# ASD2811.net
KiCad netlist of a schematic drawn in EAGLE
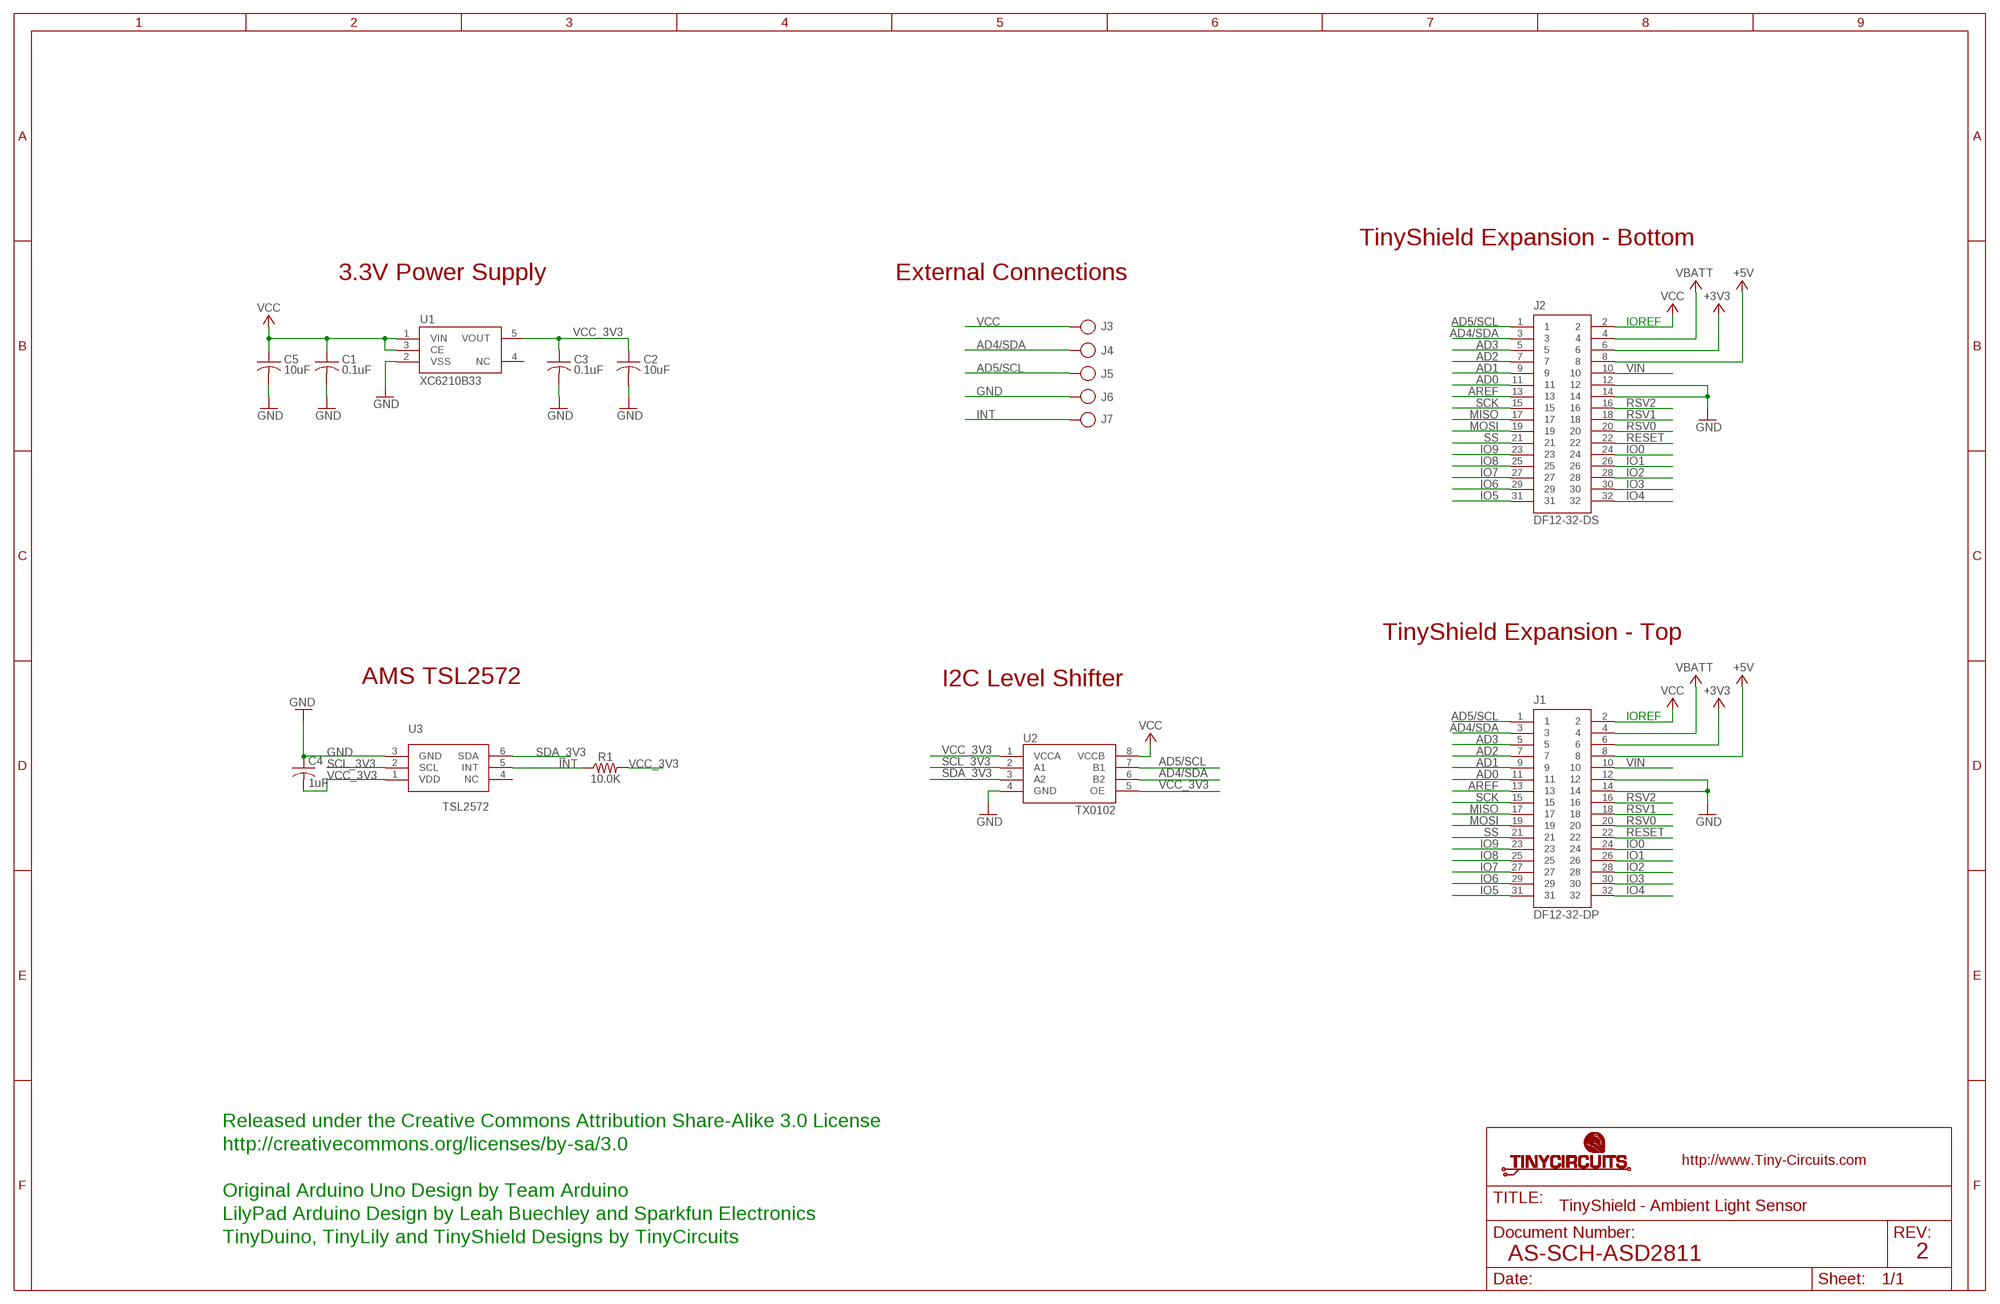
[diagram p0: schematic, sheet 1]

(export (version "E")
  (design (tool "Eeschema 10.0.6"))
  (components
    (comp (ref "C1")
      (value "0.1uF")
      (footprint "eagle-import:C0402")
      (fields (field (name "PARTNO") "AS-ITM-00008") (field (name "PARTNO_1") "AS-ITM-00008"))
      (libsource (lib "eagle-import") (part "AS-ITM-00008"))
    )
    (comp (ref "C2")
      (value "10uF")
      (footprint "eagle-import:C0805")
      (fields (field (name "PARTNO") "AS-ITM-00045") (field (name "PARTNO_1") "AS-ITM-00045"))
      (libsource (lib "eagle-import") (part "AS-ITM-00045"))
    )
    (comp (ref "C3")
      (value "0.1uF")
      (footprint "eagle-import:C0402")
      (fields (field (name "PARTNO") "AS-ITM-00008") (field (name "PARTNO_1") "AS-ITM-00008"))
      (libsource (lib "eagle-import") (part "AS-ITM-00008"))
    )
    (comp (ref "C4")
      (value "1uF")
      (footprint "eagle-import:C0402")
      (fields (field (name "PARTNO") "AS-ITM-00105"))
      (libsource (lib "eagle-import") (part "AS-ITM-00105"))
    )
    (comp (ref "C5")
      (value "10uF")
      (footprint "eagle-import:C0805")
      (fields (field (name "PARTNO") "AS-ITM-00045"))
      (libsource (lib "eagle-import") (part "AS-ITM-00045"))
    )
    (comp (ref "J1")
      (value "DF12-32-DP")
      (footprint "eagle-import:DF12-32-DP")
      (fields (field (name "PARTNO") "AS-ITM-00015") (field (name "PARTNO_1") "AS-ITM-00015"))
      (libsource (lib "eagle-import") (part "AS-ITM-00015"))
    )
    (comp (ref "J2")
      (value "DF12-32-DS")
      (footprint "eagle-import:DF12-32-DS")
      (fields (field (name "PARTNO") "AS-ITM-00012") (field (name "PARTNO_1") "AS-ITM-00012"))
      (libsource (lib "eagle-import") (part "AS-ITM-00012"))
    )
    (comp (ref "J3")
      (value "PIN_1X.1\"")
      (footprint "eagle-import:1X.1_")
      (libsource (lib "eagle-import") (part "PIN_1X.1{dblquote}"))
    )
    (comp (ref "J4")
      (value "PIN_1X.1\"")
      (footprint "eagle-import:1X.1_")
      (libsource (lib "eagle-import") (part "PIN_1X.1{dblquote}"))
    )
    (comp (ref "J5")
      (value "PIN_1X.1\"")
      (footprint "eagle-import:1X.1_")
      (libsource (lib "eagle-import") (part "PIN_1X.1{dblquote}"))
    )
    (comp (ref "J6")
      (value "PIN_1X.1\"")
      (footprint "eagle-import:1X.1_")
      (libsource (lib "eagle-import") (part "PIN_1X.1{dblquote}"))
    )
    (comp (ref "J7")
      (value "PIN_1X.1\"")
      (footprint "eagle-import:1X.1_")
      (libsource (lib "eagle-import") (part "PIN_1X.1{dblquote}"))
    )
    (comp (ref "R1")
      (value "10.0K")
      (footprint "eagle-import:0402")
      (fields (field (name "PARTNO") "AS-ITM-00032"))
      (libsource (lib "eagle-import") (part "AS-ITM-00032"))
    )
    (comp (ref "U1")
      (value "XC6210B33")
      (footprint "eagle-import:SOT-25")
      (fields (field (name "PARTNO") "AS-ITM-00046"))
      (libsource (lib "eagle-import") (part "AS-ITM-00046"))
    )
    (comp (ref "U2")
      (value "TX0102")
      (footprint "eagle-import:DQE(R-PX2SON-N8)")
      (fields (field (name "PARTNO") "AS-ITM-00073"))
      (libsource (lib "eagle-import") (part "AS-ITM-00073"))
    )
    (comp (ref "U3")
      (value "TSL2572")
      (footprint "eagle-import:TSL2572")
      (libsource (lib "eagle-import") (part "AS-ITM-00116"))
    )
  )
  (nets
    (net (code "1") (name "+3V3") (class "Default")
      (node (ref "J1") (pin "6") (pinfunction "6_6") (pintype "bidirectional"))
      (node (ref "J2") (pin "6") (pinfunction "6_6") (pintype "bidirectional"))
    )
    (net (code "2") (name "+5V") (class "Default")
      (node (ref "J1") (pin "8") (pinfunction "8_8") (pintype "bidirectional"))
      (node (ref "J2") (pin "8") (pinfunction "8_8") (pintype "bidirectional"))
    )
    (net (code "3") (name "/AD0") (class "Default")
      (node (ref "J1") (pin "11") (pinfunction "11_11") (pintype "bidirectional"))
      (node (ref "J2") (pin "11") (pinfunction "11_11") (pintype "bidirectional"))
    )
    (net (code "4") (name "/AD1") (class "Default")
      (node (ref "J1") (pin "9") (pinfunction "9_9") (pintype "bidirectional"))
      (node (ref "J2") (pin "9") (pinfunction "9_9") (pintype "bidirectional"))
    )
    (net (code "5") (name "/AD2") (class "Default")
      (node (ref "J1") (pin "7") (pinfunction "7_7") (pintype "bidirectional"))
      (node (ref "J2") (pin "7") (pinfunction "7_7") (pintype "bidirectional"))
    )
    (net (code "6") (name "/AD3") (class "Default")
      (node (ref "J1") (pin "5") (pinfunction "5_5") (pintype "bidirectional"))
      (node (ref "J2") (pin "5") (pinfunction "5_5") (pintype "bidirectional"))
    )
    (net (code "7") (name "/AD4{slash}SDA") (class "Default")
      (node (ref "J1") (pin "3") (pinfunction "3_3") (pintype "bidirectional"))
      (node (ref "J2") (pin "3") (pinfunction "3_3") (pintype "bidirectional"))
      (node (ref "J4") (pin "1") (pinfunction "1_1") (pintype "bidirectional"))
      (node (ref "U2") (pin "6") (pinfunction "B2_6") (pintype "bidirectional"))
    )
    (net (code "8") (name "/AD5{slash}SCL") (class "Default")
      (node (ref "J1") (pin "1") (pinfunction "1_1") (pintype "bidirectional"))
      (node (ref "J2") (pin "1") (pinfunction "1_1") (pintype "bidirectional"))
      (node (ref "J5") (pin "1") (pinfunction "1_1") (pintype "bidirectional"))
      (node (ref "U2") (pin "7") (pinfunction "B1_7") (pintype "bidirectional"))
    )
    (net (code "9") (name "/AREF") (class "Default")
      (node (ref "J1") (pin "13") (pinfunction "13_13") (pintype "bidirectional"))
      (node (ref "J2") (pin "13") (pinfunction "13_13") (pintype "bidirectional"))
    )
    (net (code "10") (name "/INT") (class "Default")
      (node (ref "J7") (pin "1") (pinfunction "1_1") (pintype "bidirectional"))
      (node (ref "R1") (pin "1") (pinfunction "1_1") (pintype "passive"))
      (node (ref "U3") (pin "5") (pinfunction "INT_5") (pintype "bidirectional"))
    )
    (net (code "11") (name "/IO0") (class "Default")
      (node (ref "J1") (pin "24") (pinfunction "24_24") (pintype "bidirectional"))
      (node (ref "J2") (pin "24") (pinfunction "24_24") (pintype "bidirectional"))
    )
    (net (code "12") (name "/IO1") (class "Default")
      (node (ref "J1") (pin "26") (pinfunction "26_26") (pintype "bidirectional"))
      (node (ref "J2") (pin "26") (pinfunction "26_26") (pintype "bidirectional"))
    )
    (net (code "13") (name "/IO2") (class "Default")
      (node (ref "J1") (pin "28") (pinfunction "28_28") (pintype "bidirectional"))
      (node (ref "J2") (pin "28") (pinfunction "28_28") (pintype "bidirectional"))
    )
    (net (code "14") (name "/IO3") (class "Default")
      (node (ref "J1") (pin "30") (pinfunction "30_30") (pintype "bidirectional"))
      (node (ref "J2") (pin "30") (pinfunction "30_30") (pintype "bidirectional"))
    )
    (net (code "15") (name "/IO4") (class "Default")
      (node (ref "J1") (pin "32") (pinfunction "32_32") (pintype "bidirectional"))
      (node (ref "J2") (pin "32") (pinfunction "32_32") (pintype "bidirectional"))
    )
    (net (code "16") (name "/IO5") (class "Default")
      (node (ref "J1") (pin "31") (pinfunction "31_31") (pintype "bidirectional"))
      (node (ref "J2") (pin "31") (pinfunction "31_31") (pintype "bidirectional"))
    )
    (net (code "17") (name "/IO6") (class "Default")
      (node (ref "J1") (pin "29") (pinfunction "29_29") (pintype "bidirectional"))
      (node (ref "J2") (pin "29") (pinfunction "29_29") (pintype "bidirectional"))
    )
    (net (code "18") (name "/IO7") (class "Default")
      (node (ref "J1") (pin "27") (pinfunction "27_27") (pintype "bidirectional"))
      (node (ref "J2") (pin "27") (pinfunction "27_27") (pintype "bidirectional"))
    )
    (net (code "19") (name "/IO8") (class "Default")
      (node (ref "J1") (pin "25") (pinfunction "25_25") (pintype "bidirectional"))
      (node (ref "J2") (pin "25") (pinfunction "25_25") (pintype "bidirectional"))
    )
    (net (code "20") (name "/IO9") (class "Default")
      (node (ref "J1") (pin "23") (pinfunction "23_23") (pintype "bidirectional"))
      (node (ref "J2") (pin "23") (pinfunction "23_23") (pintype "bidirectional"))
    )
    (net (code "21") (name "/MISO") (class "Default")
      (node (ref "J1") (pin "17") (pinfunction "17_17") (pintype "bidirectional"))
      (node (ref "J2") (pin "17") (pinfunction "17_17") (pintype "bidirectional"))
    )
    (net (code "22") (name "/MOSI") (class "Default")
      (node (ref "J1") (pin "19") (pinfunction "19_19") (pintype "bidirectional"))
      (node (ref "J2") (pin "19") (pinfunction "19_19") (pintype "bidirectional"))
    )
    (net (code "23") (name "/RESET") (class "Default")
      (node (ref "J1") (pin "22") (pinfunction "22_22") (pintype "bidirectional"))
      (node (ref "J2") (pin "22") (pinfunction "22_22") (pintype "bidirectional"))
    )
    (net (code "24") (name "/RSV0") (class "Default")
      (node (ref "J1") (pin "20") (pinfunction "20_20") (pintype "bidirectional"))
      (node (ref "J2") (pin "20") (pinfunction "20_20") (pintype "bidirectional"))
    )
    (net (code "25") (name "/RSV1") (class "Default")
      (node (ref "J1") (pin "18") (pinfunction "18_18") (pintype "bidirectional"))
      (node (ref "J2") (pin "18") (pinfunction "18_18") (pintype "bidirectional"))
    )
    (net (code "26") (name "/RSV2") (class "Default")
      (node (ref "J1") (pin "16") (pinfunction "16_16") (pintype "bidirectional"))
      (node (ref "J2") (pin "16") (pinfunction "16_16") (pintype "bidirectional"))
    )
    (net (code "27") (name "/SCK") (class "Default")
      (node (ref "J1") (pin "15") (pinfunction "15_15") (pintype "bidirectional"))
      (node (ref "J2") (pin "15") (pinfunction "15_15") (pintype "bidirectional"))
    )
    (net (code "28") (name "/SCL_3V3") (class "Default")
      (node (ref "U2") (pin "2") (pinfunction "A1_2") (pintype "bidirectional"))
      (node (ref "U3") (pin "2") (pinfunction "SCL_2") (pintype "bidirectional"))
    )
    (net (code "29") (name "/SDA_3V3") (class "Default")
      (node (ref "U2") (pin "3") (pinfunction "A2_3") (pintype "bidirectional"))
      (node (ref "U3") (pin "6") (pinfunction "SDA_6") (pintype "bidirectional"))
    )
    (net (code "30") (name "/SS") (class "Default")
      (node (ref "J1") (pin "21") (pinfunction "21_21") (pintype "bidirectional"))
      (node (ref "J2") (pin "21") (pinfunction "21_21") (pintype "bidirectional"))
    )
    (net (code "31") (name "/VCC_3V3") (class "Default")
      (node (ref "C2") (pin "1") (pinfunction "1_1") (pintype "passive"))
      (node (ref "C3") (pin "1") (pinfunction "1_1") (pintype "passive"))
      (node (ref "C4") (pin "2") (pinfunction "2_2") (pintype "passive"))
      (node (ref "R1") (pin "2") (pinfunction "2_2") (pintype "passive"))
      (node (ref "U1") (pin "5") (pinfunction "VOUT_5") (pintype "bidirectional"))
      (node (ref "U2") (pin "1") (pinfunction "VCCA_1") (pintype "bidirectional"))
      (node (ref "U2") (pin "5") (pinfunction "OE_5") (pintype "bidirectional"))
      (node (ref "U3") (pin "1") (pinfunction "VDD_1") (pintype "bidirectional"))
    )
    (net (code "32") (name "/VIN") (class "Default")
      (node (ref "J1") (pin "10") (pinfunction "10_10") (pintype "bidirectional"))
      (node (ref "J2") (pin "10") (pinfunction "10_10") (pintype "bidirectional"))
    )
    (net (code "33") (name "GND") (class "Default")
      (node (ref "C1") (pin "2") (pinfunction "2_2") (pintype "passive"))
      (node (ref "C2") (pin "2") (pinfunction "2_2") (pintype "passive"))
      (node (ref "C3") (pin "2") (pinfunction "2_2") (pintype "passive"))
      (node (ref "C4") (pin "1") (pinfunction "1_1") (pintype "passive"))
      (node (ref "C5") (pin "2") (pinfunction "2_2") (pintype "passive"))
      (node (ref "J1") (pin "12") (pinfunction "12_12") (pintype "bidirectional"))
      (node (ref "J1") (pin "14") (pinfunction "14_14") (pintype "bidirectional"))
      (node (ref "J2") (pin "12") (pinfunction "12_12") (pintype "bidirectional"))
      (node (ref "J2") (pin "14") (pinfunction "14_14") (pintype "bidirectional"))
      (node (ref "J6") (pin "1") (pinfunction "1_1") (pintype "bidirectional"))
      (node (ref "U1") (pin "2") (pinfunction "VSS_2") (pintype "power_in"))
      (node (ref "U2") (pin "4") (pinfunction "GND_4") (pintype "bidirectional"))
      (node (ref "U3") (pin "3") (pinfunction "GND_3") (pintype "bidirectional"))
    )
    (net (code "34") (name "VBATT") (class "Default")
      (node (ref "J1") (pin "4") (pinfunction "4_4") (pintype "bidirectional"))
      (node (ref "J2") (pin "4") (pinfunction "4_4") (pintype "bidirectional"))
    )
    (net (code "35") (name "VCC") (class "Default")
      (node (ref "C1") (pin "1") (pinfunction "1_1") (pintype "passive"))
      (node (ref "C5") (pin "1") (pinfunction "1_1") (pintype "passive"))
      (node (ref "J1") (pin "2") (pinfunction "2_2") (pintype "bidirectional"))
      (node (ref "J2") (pin "2") (pinfunction "2_2") (pintype "bidirectional"))
      (node (ref "J3") (pin "1") (pinfunction "1_1") (pintype "bidirectional"))
      (node (ref "U1") (pin "1") (pinfunction "VIN_1") (pintype "bidirectional"))
      (node (ref "U1") (pin "3") (pinfunction "CE_3") (pintype "bidirectional"))
      (node (ref "U2") (pin "8") (pinfunction "VCCB_8") (pintype "bidirectional"))
    )
    (net (code "36") (name "unconnected-(U1-NC-Pad4)") (class "Default")
      (node (ref "U1") (pin "4") (pinfunction "NC_4") (pintype "bidirectional"))
    )
    (net (code "37") (name "unconnected-(U3-NC-Pad4)") (class "Default")
      (node (ref "U3") (pin "4") (pinfunction "NC_4") (pintype "bidirectional"))
    )
  )
)
